# oshi-fuse-board-mk-1_5x20mm.net
KiCad netlist of a schematic drawn in EAGLE
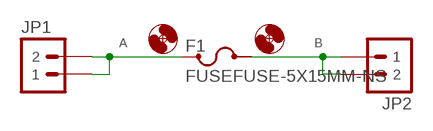
[diagram p0: schematic, sheet 1]

(export (version "E")
  (design (tool "Eeschema 10.0.6"))
  (components
    (comp (ref "F1")
      (value "FUSEFUSE-5X15MM-NS")
      (footprint "eagle-import:FUSE-2AG-NS")
      (libsource (lib "eagle-import") (part "FUSEFUSE-5X15MM-NS"))
    )
    (comp (ref "H1")
      (value "HOLE#2")
      (footprint "eagle-import:HOLE-#2")
      (libsource (lib "eagle-import") (part "HOLE#2"))
    )
    (comp (ref "H2")
      (value "HOLE#2")
      (footprint "eagle-import:HOLE-#2")
      (libsource (lib "eagle-import") (part "HOLE#2"))
    )
    (comp (ref "JP1")
      (value "M023.5MM")
      (footprint "eagle-import:SCREWTERMINAL-3.5MM-2")
      (libsource (lib "eagle-import") (part "M023.5MM"))
    )
    (comp (ref "JP2")
      (value "M023.5MM")
      (footprint "eagle-import:SCREWTERMINAL-3.5MM-2")
      (libsource (lib "eagle-import") (part "M023.5MM"))
    )
  )
  (nets
    (net (code "1") (name "/A") (class "Default")
      (node (ref "F1") (pin "1") (pinfunction "1_1") (pintype "passive"))
      (node (ref "F1") (pin "1@1") (pinfunction "1_1@1") (pintype "passive"))
      (node (ref "JP1") (pin "1") (pinfunction "1_1") (pintype "passive"))
      (node (ref "JP1") (pin "2") (pinfunction "2_2") (pintype "passive"))
    )
    (net (code "2") (name "/B") (class "Default")
      (node (ref "F1") (pin "2") (pinfunction "2_2") (pintype "passive"))
      (node (ref "JP2") (pin "1") (pinfunction "1_1") (pintype "passive"))
      (node (ref "JP2") (pin "2") (pinfunction "2_2") (pintype "passive"))
    )
  )
)
